# ArudinoShield.net
KiCad netlist of a schematic drawn in EAGLE
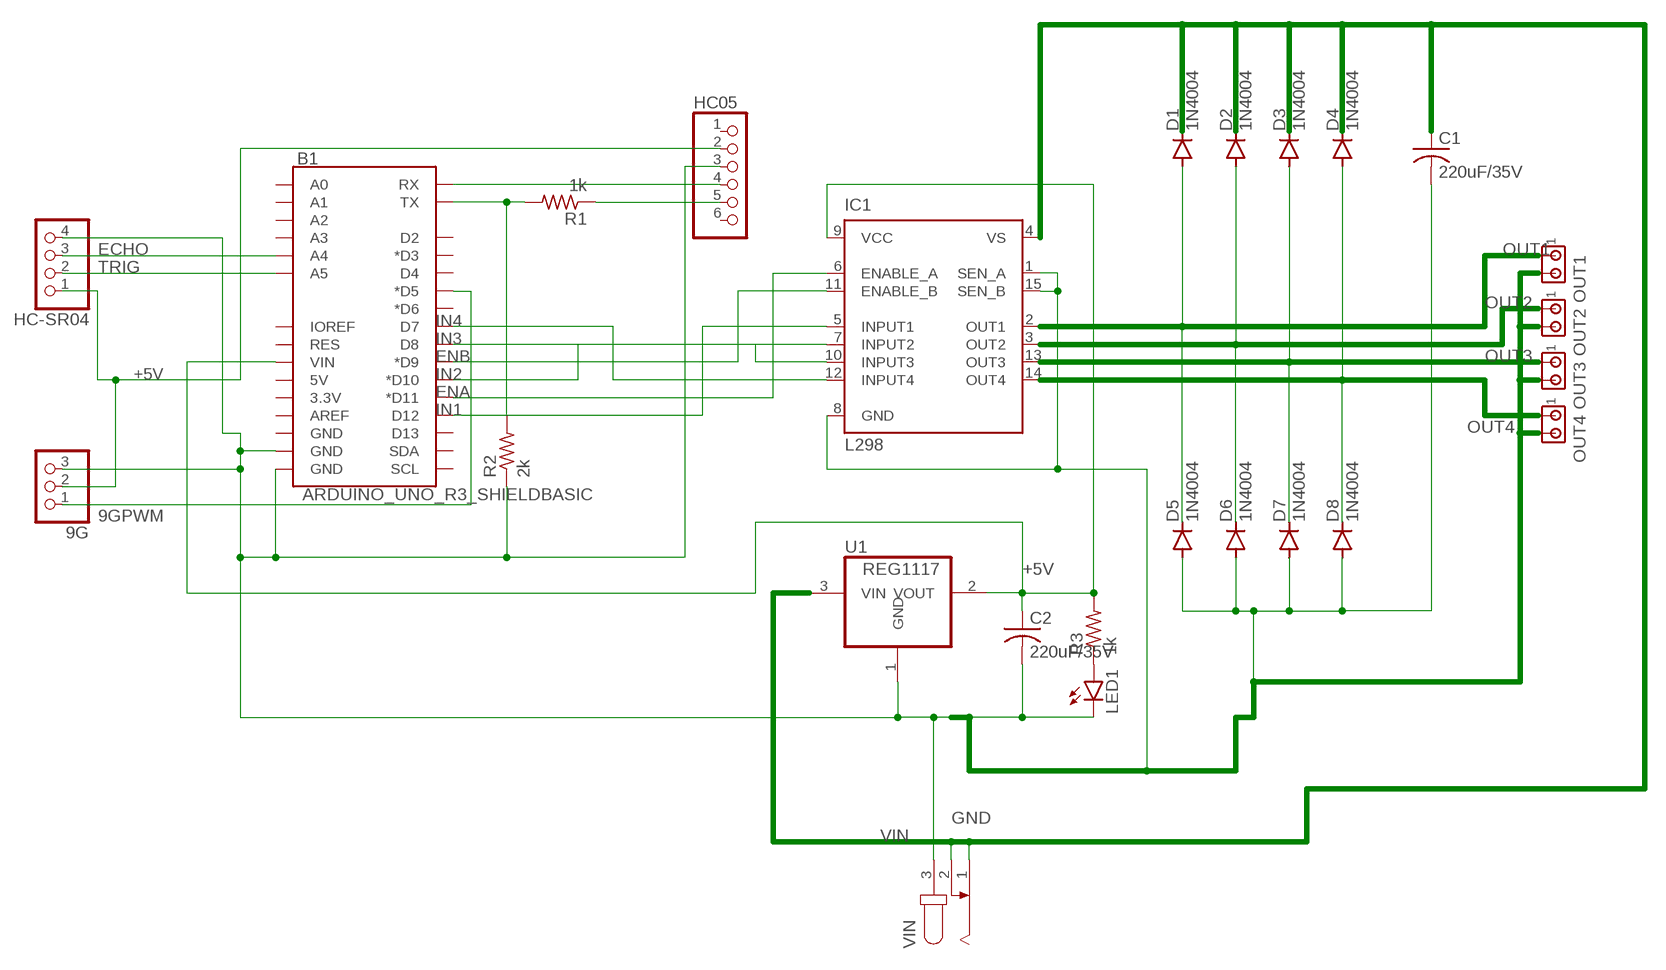
[diagram p0: schematic, sheet 1]

(export (version "E")
  (design (tool "Eeschema 10.0.6"))
  (components
    (comp (ref "9G")
      (value "PINHD-1X3")
      (footprint "eagle-import:1X03")
      (libsource (lib "eagle-import") (part "PINHD-1X3"))
    )
    (comp (ref "B1")
      (value "ARDUINO_UNO_R3_SHIELDBASIC")
      (footprint "eagle-import:UNO_R3_SHIELD")
      (libsource (lib "eagle-import") (part "ARDUINO_UNO_R3_SHIELDBASIC"))
    )
    (comp (ref "C1")
      (value "220uF/35V")
      (footprint "eagle-import:C050-024X044")
      (libsource (lib "eagle-import") (part "C-US050-024X044"))
    )
    (comp (ref "C2")
      (value "220uF/35V")
      (footprint "eagle-import:C050-024X044")
      (libsource (lib "eagle-import") (part "C-US050-024X044"))
    )
    (comp (ref "D1")
      (value "1N4004")
      (footprint "eagle-import:DO41-10")
      (libsource (lib "eagle-import") (part "1N4004"))
    )
    (comp (ref "D2")
      (value "1N4004")
      (footprint "eagle-import:DO41-10")
      (libsource (lib "eagle-import") (part "1N4004"))
    )
    (comp (ref "D3")
      (value "1N4004")
      (footprint "eagle-import:DO41-10")
      (libsource (lib "eagle-import") (part "1N4004"))
    )
    (comp (ref "D4")
      (value "1N4004")
      (footprint "eagle-import:DO41-10")
      (libsource (lib "eagle-import") (part "1N4004"))
    )
    (comp (ref "D5")
      (value "1N4004")
      (footprint "eagle-import:DO41-10")
      (libsource (lib "eagle-import") (part "1N4004"))
    )
    (comp (ref "D6")
      (value "1N4004")
      (footprint "eagle-import:DO41-10")
      (libsource (lib "eagle-import") (part "1N4004"))
    )
    (comp (ref "D7")
      (value "1N4004")
      (footprint "eagle-import:DO41-10")
      (libsource (lib "eagle-import") (part "1N4004"))
    )
    (comp (ref "D8")
      (value "1N4004")
      (footprint "eagle-import:DO41-10")
      (libsource (lib "eagle-import") (part "1N4004"))
    )
    (comp (ref "HC-SR04")
      (value "PINHD-1X4")
      (footprint "eagle-import:1X04")
      (libsource (lib "eagle-import") (part "PINHD-1X4"))
    )
    (comp (ref "HC05")
      (value "PINHD-1X6/90")
      (footprint "eagle-import:1X06_90")
      (libsource (lib "eagle-import") (part "PINHD-1X6/90"))
    )
    (comp (ref "IC1")
      (value "L298")
      (footprint "eagle-import:MULTIWATT-15")
      (fields (field (name "MPN") "L298N"))
      (libsource (lib "eagle-import") (part "L298"))
    )
    (comp (ref "LED1")
      (value "LED5MM")
      (footprint "eagle-import:LED5MM")
      (libsource (lib "eagle-import") (part "LED5MM"))
    )
    (comp (ref "OUT1")
      (value "MTA02-156")
      (footprint "eagle-import:1X2MTA")
      (libsource (lib "eagle-import") (part "MTA02-156"))
    )
    (comp (ref "OUT2")
      (value "MTA02-156")
      (footprint "eagle-import:1X2MTA")
      (libsource (lib "eagle-import") (part "MTA02-156"))
    )
    (comp (ref "OUT3")
      (value "MTA02-156")
      (footprint "eagle-import:1X2MTA")
      (libsource (lib "eagle-import") (part "MTA02-156"))
    )
    (comp (ref "OUT4")
      (value "MTA02-156")
      (footprint "eagle-import:1X2MTA")
      (libsource (lib "eagle-import") (part "MTA02-156"))
    )
    (comp (ref "R1")
      (value "1k")
      (footprint "eagle-import:0207_10")
      (libsource (lib "eagle-import") (part "R-US_0207/10"))
    )
    (comp (ref "R2")
      (value "2k")
      (footprint "eagle-import:0207_10")
      (libsource (lib "eagle-import") (part "R-US_0207/10"))
    )
    (comp (ref "R3")
      (value "1k")
      (footprint "eagle-import:0207_10")
      (libsource (lib "eagle-import") (part "R-US_0207/10"))
    )
    (comp (ref "U1")
      (value "REG1117")
      (footprint "eagle-import:SOT223")
      (libsource (lib "eagle-import") (part "REG1117"))
    )
    (comp (ref "VIN")
      (value "JACK-PLUG1")
      (footprint "eagle-import:SPC4078")
      (libsource (lib "eagle-import") (part "JACK-PLUG1"))
    )
  )
  (nets
    (net (code "1") (name "/+5V") (class "Default")
      (node (ref "9G") (pin "2") (pinfunction "2_2") (pintype "passive"))
      (node (ref "B1") (pin "VIN") (pinfunction "VIN_VIN") (pintype "bidirectional"))
      (node (ref "C2") (pin "1") (pinfunction "1_1") (pintype "passive"))
      (node (ref "HC-SR04") (pin "1") (pinfunction "1_1") (pintype "passive"))
      (node (ref "HC05") (pin "2") (pinfunction "2_2") (pintype "passive"))
      (node (ref "IC1") (pin "9") (pinfunction "VCC_9") (pintype "power_in"))
      (node (ref "R3") (pin "2") (pinfunction "2_2") (pintype "passive"))
      (node (ref "U1") (pin "2") (pinfunction "VOUT_2") (pintype "output"))
    )
    (net (code "2") (name "/9GPWM") (class "Default")
      (node (ref "9G") (pin "1") (pinfunction "1_1") (pintype "passive"))
      (node (ref "B1") (pin "D5") (pinfunction "*D5_D5") (pintype "bidirectional"))
    )
    (net (code "3") (name "/ECHO") (class "Default")
      (node (ref "B1") (pin "A4") (pinfunction "A4_A4") (pintype "bidirectional"))
      (node (ref "HC-SR04") (pin "3") (pinfunction "3_3") (pintype "passive"))
    )
    (net (code "4") (name "/ENA") (class "Default")
      (node (ref "B1") (pin "D11") (pinfunction "*D11_D11") (pintype "bidirectional"))
      (node (ref "IC1") (pin "6") (pinfunction "ENABLE_A_6") (pintype "input"))
    )
    (net (code "5") (name "/ENB") (class "Default")
      (node (ref "B1") (pin "D9") (pinfunction "*D9_D9") (pintype "bidirectional"))
      (node (ref "IC1") (pin "11") (pinfunction "ENABLE_B_11") (pintype "input"))
    )
    (net (code "6") (name "/GND") (class "Default")
      (node (ref "9G") (pin "3") (pinfunction "3_3") (pintype "passive"))
      (node (ref "B1") (pin "GND@0") (pinfunction "GND_GND@0") (pintype "bidirectional"))
      (node (ref "B1") (pin "GND@1") (pinfunction "GND_GND@1") (pintype "bidirectional"))
      (node (ref "C1") (pin "2") (pinfunction "2_2") (pintype "passive"))
      (node (ref "C2") (pin "2") (pinfunction "2_2") (pintype "passive"))
      (node (ref "D5") (pin "A") (pinfunction "A_A") (pintype "passive"))
      (node (ref "D6") (pin "A") (pinfunction "A_A") (pintype "passive"))
      (node (ref "D7") (pin "A") (pinfunction "A_A") (pintype "passive"))
      (node (ref "D8") (pin "A") (pinfunction "A_A") (pintype "passive"))
      (node (ref "HC-SR04") (pin "4") (pinfunction "4_4") (pintype "passive"))
      (node (ref "HC05") (pin "3") (pinfunction "3_3") (pintype "passive"))
      (node (ref "IC1") (pin "1") (pinfunction "SEN_A_1") (pintype "input"))
      (node (ref "IC1") (pin "15") (pinfunction "SEN_B_15") (pintype "input"))
      (node (ref "IC1") (pin "8") (pinfunction "GND_8") (pintype "power_in"))
      (node (ref "LED1") (pin "K") (pinfunction "C_K") (pintype "passive"))
      (node (ref "OUT1") (pin "2") (pinfunction "2_2") (pintype "passive"))
      (node (ref "OUT2") (pin "2") (pinfunction "2_2") (pintype "passive"))
      (node (ref "OUT3") (pin "2") (pinfunction "2_2") (pintype "passive"))
      (node (ref "OUT4") (pin "2") (pinfunction "2_2") (pintype "passive"))
      (node (ref "R2") (pin "1") (pinfunction "1_1") (pintype "passive"))
      (node (ref "U1") (pin "1") (pinfunction "GND_1") (pintype "power_in"))
      (node (ref "VIN") (pin "3") (pinfunction "3_3") (pintype "passive"))
    )
    (net (code "7") (name "/IN1") (class "Default")
      (node (ref "B1") (pin "D12") (pinfunction "D12_D12") (pintype "bidirectional"))
      (node (ref "IC1") (pin "5") (pinfunction "INPUT1_5") (pintype "input"))
    )
    (net (code "8") (name "/IN2") (class "Default")
      (node (ref "B1") (pin "D10") (pinfunction "*D10_D10") (pintype "bidirectional"))
      (node (ref "IC1") (pin "7") (pinfunction "INPUT2_7") (pintype "input"))
    )
    (net (code "9") (name "/IN3") (class "Default")
      (node (ref "B1") (pin "D8") (pinfunction "D8_D8") (pintype "bidirectional"))
      (node (ref "IC1") (pin "10") (pinfunction "INPUT3_10") (pintype "input"))
    )
    (net (code "10") (name "/IN4") (class "Default")
      (node (ref "B1") (pin "D7") (pinfunction "D7_D7") (pintype "bidirectional"))
      (node (ref "IC1") (pin "12") (pinfunction "INPUT4_12") (pintype "input"))
    )
    (net (code "11") (name "/OUT1") (class "Default")
      (node (ref "D1") (pin "A") (pinfunction "A_A") (pintype "passive"))
      (node (ref "D5") (pin "C") (pinfunction "C_C") (pintype "passive"))
      (node (ref "IC1") (pin "2") (pinfunction "OUT1_2") (pintype "output"))
      (node (ref "OUT1") (pin "1") (pinfunction "1_1") (pintype "passive"))
    )
    (net (code "12") (name "/OUT2") (class "Default")
      (node (ref "D2") (pin "A") (pinfunction "A_A") (pintype "passive"))
      (node (ref "D6") (pin "C") (pinfunction "C_C") (pintype "passive"))
      (node (ref "IC1") (pin "3") (pinfunction "OUT2_3") (pintype "output"))
      (node (ref "OUT2") (pin "1") (pinfunction "1_1") (pintype "passive"))
    )
    (net (code "13") (name "/OUT3") (class "Default")
      (node (ref "D3") (pin "A") (pinfunction "A_A") (pintype "passive"))
      (node (ref "D7") (pin "C") (pinfunction "C_C") (pintype "passive"))
      (node (ref "IC1") (pin "13") (pinfunction "OUT3_13") (pintype "output"))
      (node (ref "OUT3") (pin "1") (pinfunction "1_1") (pintype "passive"))
    )
    (net (code "14") (name "/OUT4") (class "Default")
      (node (ref "D4") (pin "A") (pinfunction "A_A") (pintype "passive"))
      (node (ref "D8") (pin "C") (pinfunction "C_C") (pintype "passive"))
      (node (ref "IC1") (pin "14") (pinfunction "OUT4_14") (pintype "output"))
      (node (ref "OUT4") (pin "1") (pinfunction "1_1") (pintype "passive"))
    )
    (net (code "15") (name "/TRIG") (class "Default")
      (node (ref "B1") (pin "A5") (pinfunction "A5_A5") (pintype "bidirectional"))
      (node (ref "HC-SR04") (pin "2") (pinfunction "2_2") (pintype "passive"))
    )
    (net (code "16") (name "/VIN") (class "Default")
      (node (ref "C1") (pin "1") (pinfunction "1_1") (pintype "passive"))
      (node (ref "D1") (pin "C") (pinfunction "C_C") (pintype "passive"))
      (node (ref "D2") (pin "C") (pinfunction "C_C") (pintype "passive"))
      (node (ref "D3") (pin "C") (pinfunction "C_C") (pintype "passive"))
      (node (ref "D4") (pin "C") (pinfunction "C_C") (pintype "passive"))
      (node (ref "IC1") (pin "4") (pinfunction "VS_4") (pintype "power_in"))
      (node (ref "U1") (pin "3") (pinfunction "VIN_3") (pintype "input"))
      (node (ref "VIN") (pin "1") (pinfunction "1_1") (pintype "passive"))
      (node (ref "VIN") (pin "2") (pinfunction "2_2") (pintype "passive"))
    )
    (net (code "17") (name "Net-(B1-PadRX)") (class "Default")
      (node (ref "B1") (pin "RX") (pinfunction "RX_RX") (pintype "bidirectional"))
      (node (ref "HC05") (pin "4") (pinfunction "4_4") (pintype "passive"))
    )
    (net (code "18") (name "Net-(B1-PadTX)") (class "Default")
      (node (ref "B1") (pin "TX") (pinfunction "TX_TX") (pintype "bidirectional"))
      (node (ref "R1") (pin "2") (pinfunction "2_2") (pintype "passive"))
      (node (ref "R2") (pin "2") (pinfunction "2_2") (pintype "passive"))
    )
    (net (code "19") (name "Net-(HC05-Pad5)") (class "Default")
      (node (ref "HC05") (pin "5") (pinfunction "5_5") (pintype "passive"))
      (node (ref "R1") (pin "1") (pinfunction "1_1") (pintype "passive"))
    )
    (net (code "20") (name "Net-(LED1-PadA)") (class "Default")
      (node (ref "LED1") (pin "A") (pinfunction "A_A") (pintype "passive"))
      (node (ref "R3") (pin "1") (pinfunction "1_1") (pintype "passive"))
    )
    (net (code "21") (name "unconnected-(B1-*D3-PadD3)") (class "Default")
      (node (ref "B1") (pin "D3") (pinfunction "*D3_D3") (pintype "bidirectional"))
    )
    (net (code "22") (name "unconnected-(B1-*D6-PadD6)") (class "Default")
      (node (ref "B1") (pin "D6") (pinfunction "*D6_D6") (pintype "bidirectional"))
    )
    (net (code "23") (name "unconnected-(B1-GND-PadGND@2)") (class "Default")
      (node (ref "B1") (pin "GND@2") (pinfunction "GND_GND@2") (pintype "bidirectional"))
    )
    (net (code "24") (name "unconnected-(B1-Pad3.3V)") (class "Default")
      (node (ref "B1") (pin "3.3V") (pinfunction "3.3V_3.3V") (pintype "bidirectional"))
    )
    (net (code "25") (name "unconnected-(B1-Pad5V)") (class "Default")
      (node (ref "B1") (pin "5V") (pinfunction "5V_5V") (pintype "bidirectional"))
    )
    (net (code "26") (name "unconnected-(B1-PadA0)") (class "Default")
      (node (ref "B1") (pin "A0") (pinfunction "A0_A0") (pintype "bidirectional"))
    )
    (net (code "27") (name "unconnected-(B1-PadA1)") (class "Default")
      (node (ref "B1") (pin "A1") (pinfunction "A1_A1") (pintype "bidirectional"))
    )
    (net (code "28") (name "unconnected-(B1-PadA2)") (class "Default")
      (node (ref "B1") (pin "A2") (pinfunction "A2_A2") (pintype "bidirectional"))
    )
    (net (code "29") (name "unconnected-(B1-PadA3)") (class "Default")
      (node (ref "B1") (pin "A3") (pinfunction "A3_A3") (pintype "bidirectional"))
    )
    (net (code "30") (name "unconnected-(B1-PadAREF)") (class "Default")
      (node (ref "B1") (pin "AREF") (pinfunction "AREF_AREF") (pintype "bidirectional"))
    )
    (net (code "31") (name "unconnected-(B1-PadD2)") (class "Default")
      (node (ref "B1") (pin "D2") (pinfunction "D2_D2") (pintype "bidirectional"))
    )
    (net (code "32") (name "unconnected-(B1-PadD4)") (class "Default")
      (node (ref "B1") (pin "D4") (pinfunction "D4_D4") (pintype "bidirectional"))
    )
    (net (code "33") (name "unconnected-(B1-PadD13)") (class "Default")
      (node (ref "B1") (pin "D13") (pinfunction "D13_D13") (pintype "bidirectional"))
    )
    (net (code "34") (name "unconnected-(B1-PadIOREF)") (class "Default")
      (node (ref "B1") (pin "IOREF") (pinfunction "IOREF_IOREF") (pintype "bidirectional"))
    )
    (net (code "35") (name "unconnected-(B1-PadRES)") (class "Default")
      (node (ref "B1") (pin "RES") (pinfunction "RES_RES") (pintype "bidirectional"))
    )
    (net (code "36") (name "unconnected-(B1-PadSCL)") (class "Default")
      (node (ref "B1") (pin "SCL") (pinfunction "SCL_SCL") (pintype "bidirectional"))
    )
    (net (code "37") (name "unconnected-(B1-PadSDA)") (class "Default")
      (node (ref "B1") (pin "SDA") (pinfunction "SDA_SDA") (pintype "bidirectional"))
    )
    (net (code "38") (name "unconnected-(HC05-Pad1)") (class "Default")
      (node (ref "HC05") (pin "1") (pinfunction "1_1") (pintype "passive"))
    )
    (net (code "39") (name "unconnected-(HC05-Pad6)") (class "Default")
      (node (ref "HC05") (pin "6") (pinfunction "6_6") (pintype "passive"))
    )
  )
)
